# FlexEMG_v0r0_BATT-CHARGER.net
KiCad netlist of a schematic drawn in Altium Designer
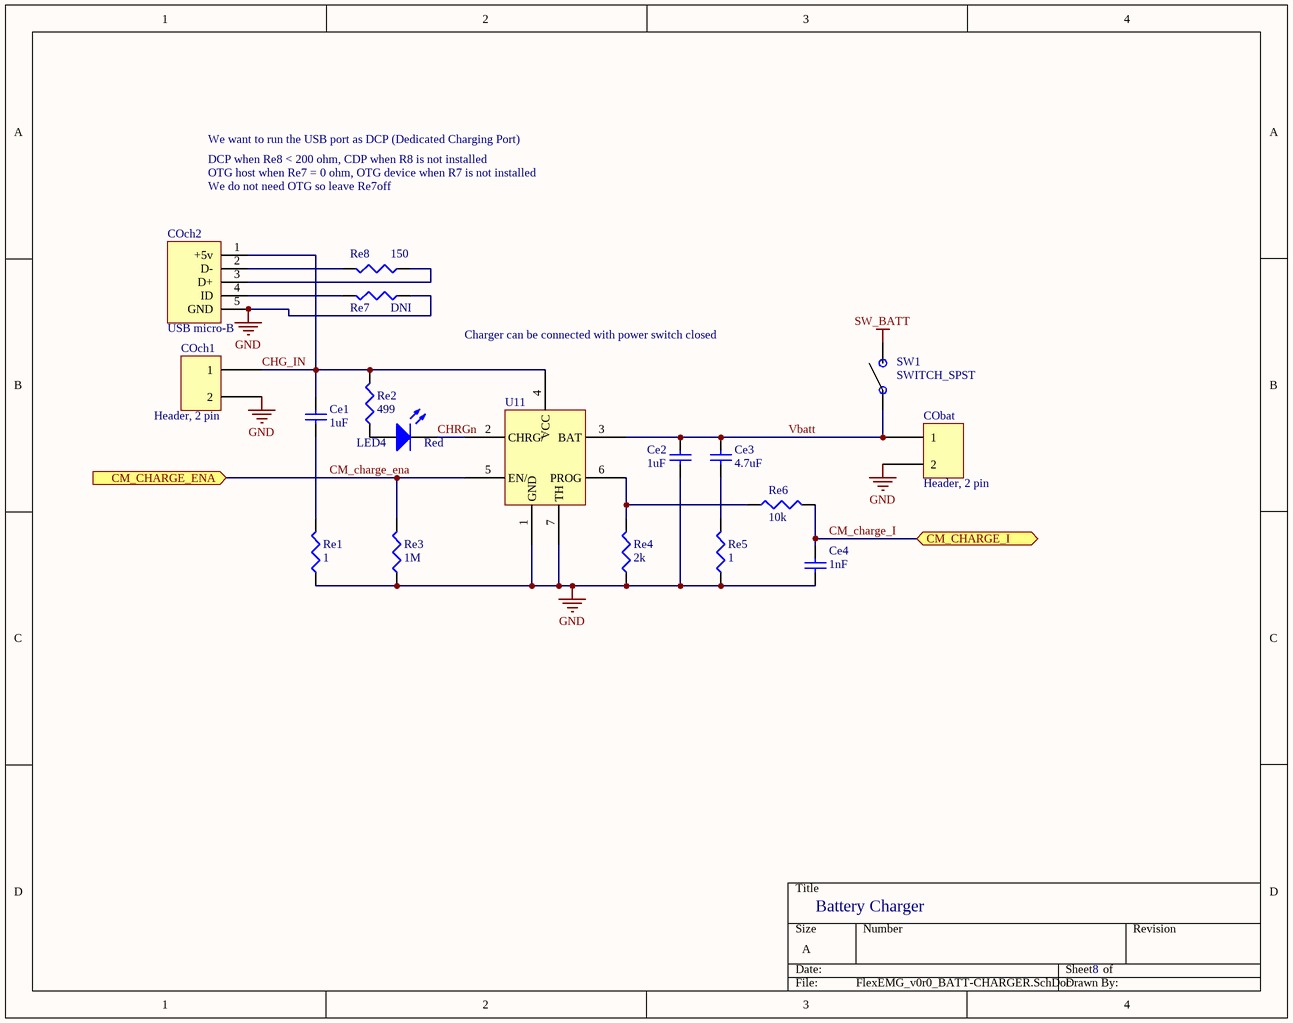
[diagram p0: FlexEMG_v0r0_BATT-CHARGER.SchDoc]

(export (version "E")
  (design (tool "Eeschema 10.0.6"))
  (components
    (comp (ref "Ce1")
      (value "1uF")
      (footprint "c0402-TDK-C")
      (description "CAP CER 1UF 16V X5R 0402")
      (fields (field (name "MANUFACTURER") "TDK") (field (name "Comment") "C1005X5R1C105M050BC"))
      (libsource (lib "Custom") (part "Cap"))
    )
    (comp (ref "Ce2")
      (value "1uF")
      (footprint "c0402-TDK-C")
      (description "CAP CER 1UF 16V X5R 0402")
      (fields (field (name "MANUFACTURER") "TDK") (field (name "Comment") "C1005X5R1C105M050BC"))
      (libsource (lib "Custom") (part "Cap"))
    )
    (comp (ref "Ce3")
      (value "4.7uF")
      (footprint "c0603-Murata-GR")
      (description "CAP CER 4.7UF 35V X5R 0603")
      (fields (field (name "MANUFACTURER") "Murata") (field (name "Comment") "GRM188R6YA475KE15D"))
      (libsource (lib "Custom") (part "Cap"))
    )
    (comp (ref "Ce4")
      (value "1nF")
      (footprint "c0402-Murata-GR")
      (description "CAP CER 1000PF 50V X5R 0402")
      (fields (field (name "MANUFACTURER") "Murata") (field (name "Comment") "GRM155R61H102KA01D"))
      (libsource (lib "Custom") (part "Cap"))
    )
    (comp (ref "CObat")
      (value "Header, 2 pin")
      (footprint "Header, 2 pin, 2mm(79mil)")
      (description "Header 1x2")
      (fields (field (name "MANUFACTURER") "Samtec"))
      (libsource (lib "") (part "Header, 2 pin_1"))
    )
    (comp (ref "COch1")
      (value "Header, 2 pin")
      (footprint "Header, 2 pin, 2mm(79mil)")
      (description "Header 1x2")
      (fields (field (name "MANUFACTURER") "Samtec"))
      (libsource (lib "CM") (part "Header, 2 pin"))
    )
    (comp (ref "COch2")
      (value "USB micro-B")
      (footprint "USB-microB_amp_10118194-0001LF")
      (description "USB micro-B connector")
      (fields (field (name "MANUFACTURER") "Amphenol"))
      (libsource (lib "CM") (part "USB-microB"))
    )
    (comp (ref "LED4")
      (value "~")
      (footprint "LED-0603")
      (description "LED RED CLEAR 0603 SMD")
      (fields (field (name "MANUFACTURER") "Rohm") (field (name "COLOR") "Red"))
      (libsource (lib "Custom") (part "LED"))
    )
    (comp (ref "Re1")
      (value "1")
      (footprint "0402_p")
      (description "RES SMD 1 OHM 1% 1/6W 0402")
      (fields (field (name "MANUFACTURER") "Panasonic") (field (name "POWER") "1/6W"))
      (libsource (lib "Custom") (part "Resistor"))
    )
    (comp (ref "Re2")
      (value "499")
      (footprint "0402_p")
      (description "RES SMD 499 OHM 1% 1/10W 0402")
      (fields (field (name "MANUFACTURER") "Panasonic") (field (name "POWER") "1/10W"))
      (libsource (lib "Custom") (part "Resistor"))
    )
    (comp (ref "Re3")
      (value "1M")
      (footprint "0402_p")
      (description "RES SMD 1M OHM 1% 1/10W 0402")
      (fields (field (name "MANUFACTURER") "Panasonic") (field (name "POWER") "1/10W"))
      (libsource (lib "Custom") (part "Resistor"))
    )
    (comp (ref "Re4")
      (value "2k")
      (footprint "0402_p")
      (description "RES SMD 2K OHM 1% 1/10W 0402")
      (fields (field (name "MANUFACTURER") "Panasonic") (field (name "POWER") "1/10W"))
      (libsource (lib "Custom") (part "Resistor"))
    )
    (comp (ref "Re5")
      (value "1")
      (footprint "0402_p")
      (description "RES SMD 1 OHM 1% 1/6W 0402")
      (fields (field (name "MANUFACTURER") "Panasonic") (field (name "POWER") "1/6W"))
      (libsource (lib "Custom") (part "Resistor"))
    )
    (comp (ref "Re6")
      (value "10k")
      (footprint "0402_p")
      (description "RES SMD 10K OHM 1% 1/10W 0402")
      (fields (field (name "MANUFACTURER") "Panasonic") (field (name "POWER") "1/10W"))
      (libsource (lib "Custom") (part "Resistor"))
    )
    (comp (ref "Re7")
      (value "DNI")
      (footprint "0402_p")
      (description "Resistor")
      (fields (field (name "MANUFACTURER") "Panasonic") (field (name "POWER") "1/10W"))
      (libsource (lib "Custom") (part "Resistor"))
    )
    (comp (ref "Re8")
      (value "150")
      (footprint "0402_p")
      (description "RES SMD 150 OHM 5% 1/5W 0402")
      (fields (field (name "MANUFACTURER") "Panasonic") (field (name "POWER") "1/10W"))
      (libsource (lib "Custom") (part "Resistor"))
    )
    (comp (ref "SW1")
      (value "SWITCH_SPST")
      (footprint "SWITCH_SPST_CHS-01TB")
      (description "SWITCH SLIDE DIP SPST 100MA 6V")
      (fields (field (name "MANUFACTURER") "Copal"))
      (libsource (lib "CM") (part "SWITCH_SPST"))
    )
    (comp (ref "U11")
      (value "LTC4065EDC#TRMPBF")
      (footprint "DFN-6_LT")
      (description "IC CHARGER BATT LI-ON 6-DFN")
      (fields (field (name "MANUFACTURER") "LT"))
      (libsource (lib "Custom") (part "LTC4065EDC"))
    )
  )
  (nets
    (net (code "1") (name "/CHG_IN") (class "Default")
      (node (ref "COch1") (pin "1") (pinfunction "1_1") (pintype "passive"))
      (node (ref "COch2") (pin "1") (pinfunction "+5v_1") (pintype "power_in"))
      (node (ref "Ce1") (pin "2") (pinfunction "2_2") (pintype "passive"))
      (node (ref "Re2") (pin "2") (pinfunction "2_2") (pintype "passive"))
      (node (ref "U11") (pin "4") (pinfunction "VCC_4") (pintype "passive"))
    )
    (net (code "2") (name "/CHRGn") (class "Default")
      (node (ref "LED4") (pin "2") (pinfunction "K_2") (pintype "passive"))
      (node (ref "U11") (pin "2") (pinfunction "CHRG/_2") (pintype "passive"))
    )
    (net (code "3") (name "/CM_charge_I") (class "Default")
      (node (ref "Ce4") (pin "2") (pinfunction "2_2") (pintype "passive"))
      (node (ref "Re6") (pin "2") (pinfunction "2_2") (pintype "passive"))
    )
    (net (code "4") (name "/CM_charge_ena") (class "Default")
      (node (ref "Re3") (pin "2") (pinfunction "2_2") (pintype "passive"))
      (node (ref "U11") (pin "5") (pinfunction "EN/_5") (pintype "passive"))
    )
    (net (code "5") (name "/Vbatt") (class "Default")
      (node (ref "CObat") (pin "1") (pinfunction "1_1") (pintype "passive"))
      (node (ref "Ce2") (pin "2") (pinfunction "2_2") (pintype "passive"))
      (node (ref "Ce3") (pin "2") (pinfunction "2_2") (pintype "passive"))
      (node (ref "SW1") (pin "2") (pinfunction "2_2") (pintype "passive"))
      (node (ref "U11") (pin "3") (pinfunction "BAT_3") (pintype "passive"))
    )
    (net (code "6") (name "GND") (class "Default")
      (node (ref "CObat") (pin "2") (pinfunction "2_2") (pintype "passive"))
      (node (ref "COch1") (pin "2") (pinfunction "2_2") (pintype "passive"))
      (node (ref "COch2") (pin "5") (pinfunction "GND_5") (pintype "power_in"))
      (node (ref "Ce2") (pin "1") (pinfunction "1_1") (pintype "passive"))
      (node (ref "Ce4") (pin "1") (pinfunction "1_1") (pintype "passive"))
      (node (ref "Re1") (pin "1") (pinfunction "1_1") (pintype "passive"))
      (node (ref "Re3") (pin "1") (pinfunction "1_1") (pintype "passive"))
      (node (ref "Re4") (pin "1") (pinfunction "1_1") (pintype "passive"))
      (node (ref "Re5") (pin "1") (pinfunction "1_1") (pintype "passive"))
      (node (ref "Re7") (pin "1") (pinfunction "1_1") (pintype "passive"))
      (node (ref "U11") (pin "1") (pinfunction "GND_1") (pintype "passive"))
      (node (ref "U11") (pin "7") (pinfunction "TH_7") (pintype "passive"))
    )
    (net (code "7") (name "Net-(COch2-D+)") (class "Default")
      (node (ref "COch2") (pin "3") (pinfunction "D+_3") (pintype "passive"))
      (node (ref "Re8") (pin "1") (pinfunction "1_1") (pintype "passive"))
    )
    (net (code "8") (name "Net-(COch2-D-)") (class "Default")
      (node (ref "COch2") (pin "2") (pinfunction "D-_2") (pintype "passive"))
      (node (ref "Re8") (pin "2") (pinfunction "2_2") (pintype "passive"))
    )
    (net (code "9") (name "Net-(COch2-ID)") (class "Default")
      (node (ref "COch2") (pin "4") (pinfunction "ID_4") (pintype "passive"))
      (node (ref "Re7") (pin "2") (pinfunction "2_2") (pintype "passive"))
    )
    (net (code "10") (name "Net-(Ce1-Pad1)") (class "Default")
      (node (ref "Ce1") (pin "1") (pinfunction "1_1") (pintype "passive"))
      (node (ref "Re1") (pin "2") (pinfunction "2_2") (pintype "passive"))
    )
    (net (code "11") (name "Net-(Ce3-Pad1)") (class "Default")
      (node (ref "Ce3") (pin "1") (pinfunction "1_1") (pintype "passive"))
      (node (ref "Re5") (pin "2") (pinfunction "2_2") (pintype "passive"))
    )
    (net (code "12") (name "Net-(LED4-A)") (class "Default")
      (node (ref "LED4") (pin "1") (pinfunction "A_1") (pintype "passive"))
      (node (ref "Re2") (pin "1") (pinfunction "1_1") (pintype "passive"))
    )
    (net (code "13") (name "Net-(U11-PROG)") (class "Default")
      (node (ref "Re4") (pin "2") (pinfunction "2_2") (pintype "passive"))
      (node (ref "Re6") (pin "1") (pinfunction "1_1") (pintype "passive"))
      (node (ref "U11") (pin "6") (pinfunction "PROG_6") (pintype "passive"))
    )
    (net (code "14") (name "SW_BATT") (class "Default")
      (node (ref "SW1") (pin "1") (pinfunction "1_1") (pintype "passive"))
    )
    (net (code "15") (name "unconnected-(COch2-Pad6)") (class "Default")
      (node (ref "COch2") (pin "6") (pinfunction "6_6") (pintype "passive"))
    )
    (net (code "16") (name "unconnected-(COch2-Pad7)") (class "Default")
      (node (ref "COch2") (pin "7") (pinfunction "7_7") (pintype "passive"))
    )
    (net (code "17") (name "unconnected-(COch2-Pad8)") (class "Default")
      (node (ref "COch2") (pin "8") (pinfunction "8_8") (pintype "passive"))
    )
    (net (code "18") (name "unconnected-(COch2-Pad9)") (class "Default")
      (node (ref "COch2") (pin "9") (pinfunction "9_9") (pintype "passive"))
    )
  )
)
